# LB_BIT_oX_1IN_1OUT-MEDIUM-v03_1_1x.net
KiCad netlist of a schematic drawn in EAGLE
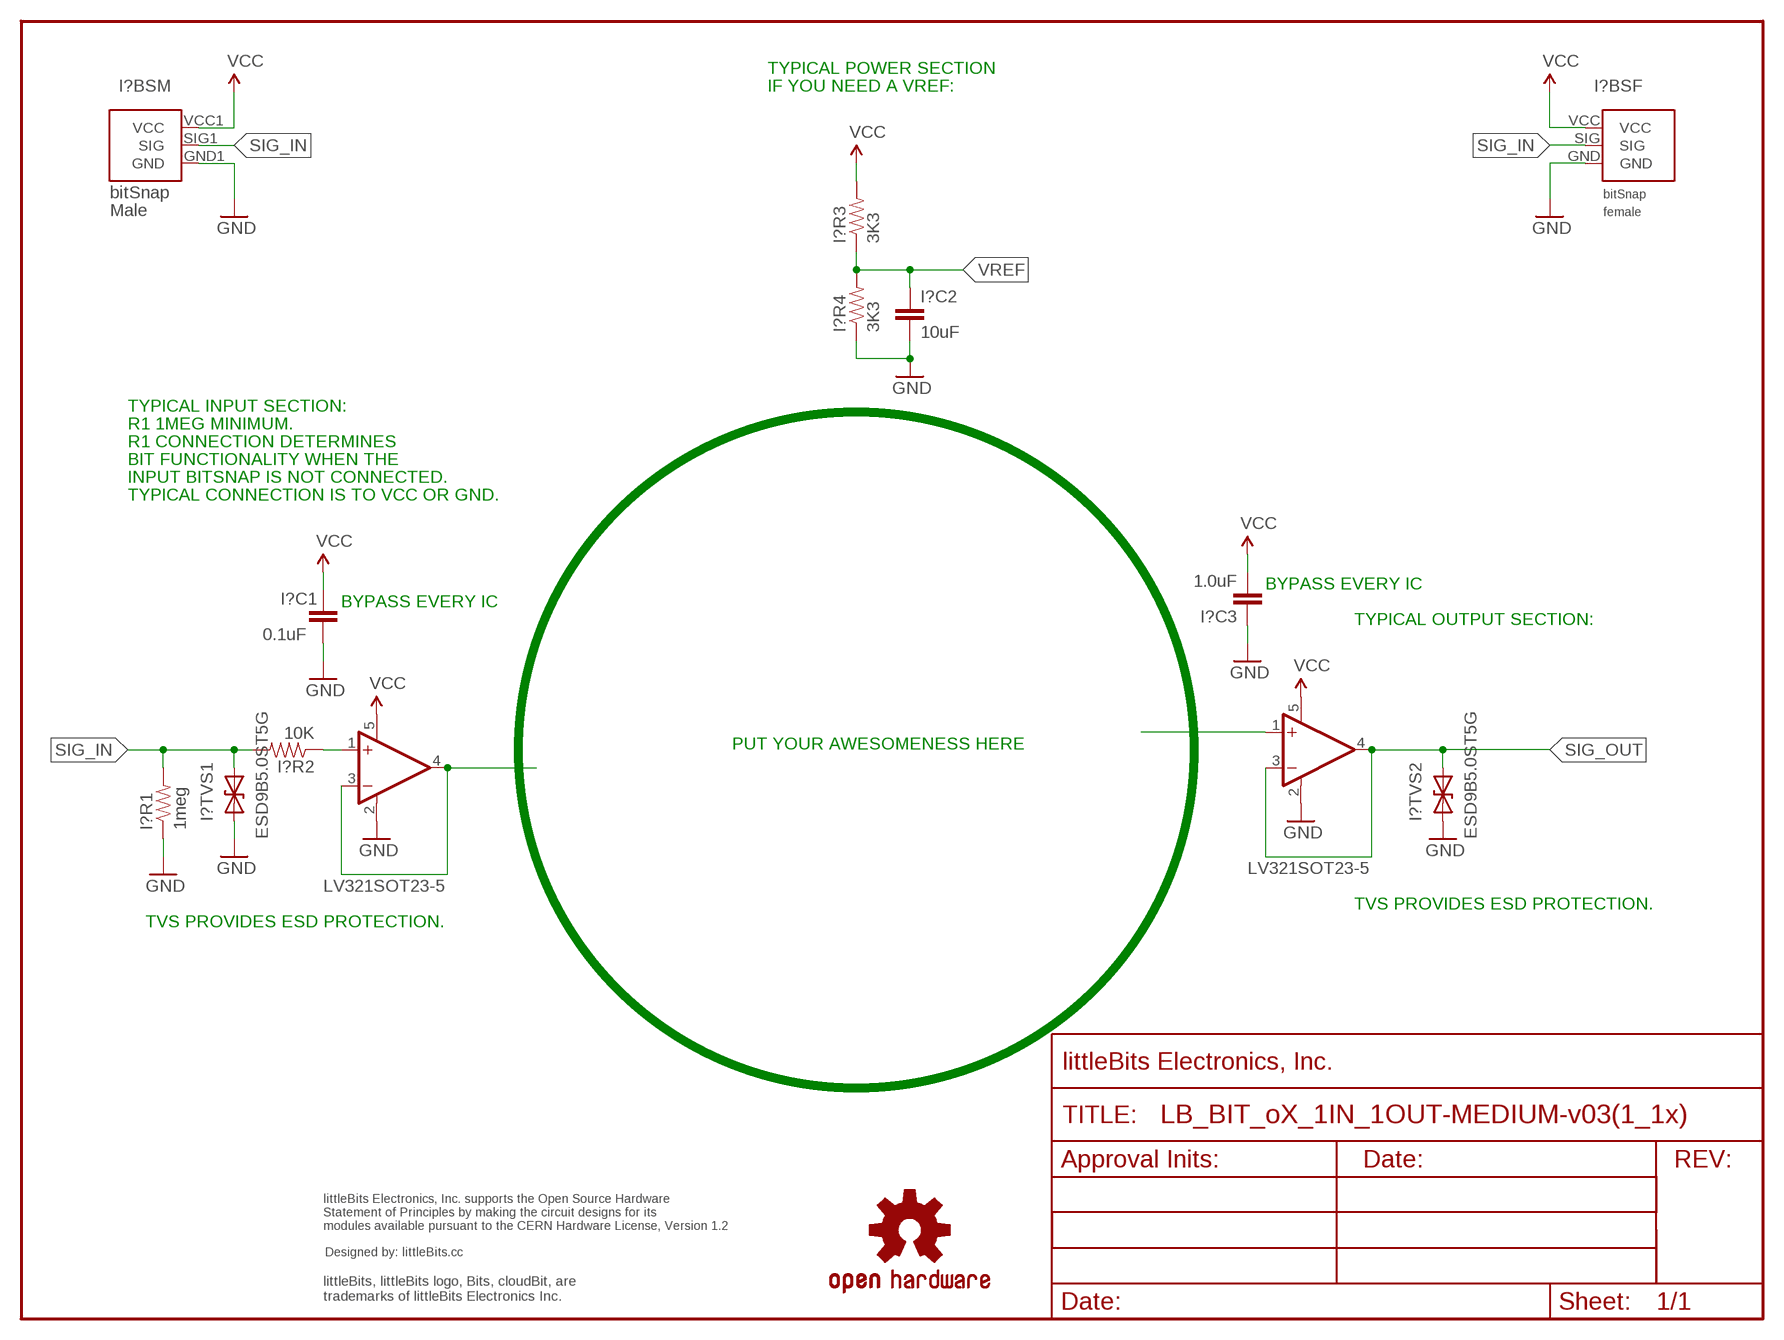
[diagram p0: schematic, sheet 1]

(export (version "E")
  (design (tool "Eeschema 10.0.6"))
  (components
    (comp (ref "I?BSF")
      (value "BITSNAP_V03_FEMALE")
      (footprint "eagle-import:BITSNAP_V03_FEMALE")
      (libsource (lib "eagle-import") (part "BITSNAP_V03_FEMALE"))
    )
    (comp (ref "I?BSM")
      (value "BITSNAP_V03_MALE")
      (footprint "eagle-import:BITSNAP_V03_MALE")
      (libsource (lib "eagle-import") (part "BITSNAP_V03_MALE"))
    )
    (comp (ref "I?C1")
      (value "0.1uF")
      (footprint "eagle-import:CAP-0603")
      (libsource (lib "eagle-import") (part "CAPCAP-0603"))
    )
    (comp (ref "I?C2")
      (value "10uF")
      (footprint "eagle-import:CAP-0603")
      (libsource (lib "eagle-import") (part "CAPCAP-0603"))
    )
    (comp (ref "I?C3")
      (value "1.0uF")
      (footprint "eagle-import:CAP-0603")
      (libsource (lib "eagle-import") (part "CAPCAP-0603"))
    )
    (comp (ref "I?R1")
      (value "1meg")
      (footprint "eagle-import:RES-0603")
      (libsource (lib "eagle-import") (part "RESISTOR0603"))
    )
    (comp (ref "I?R2")
      (value "10K")
      (footprint "eagle-import:RES-0603")
      (libsource (lib "eagle-import") (part "RESISTOR0603"))
    )
    (comp (ref "I?R3")
      (value "3K3")
      (footprint "eagle-import:RES-0603")
      (libsource (lib "eagle-import") (part "RESISTOR0603"))
    )
    (comp (ref "I?R4")
      (value "3K3")
      (footprint "eagle-import:RES-0603")
      (libsource (lib "eagle-import") (part "RESISTOR0603"))
    )
    (comp (ref "I?TVS1")
      (value "ESD9B5.0ST5G")
      (footprint "eagle-import:SOD-923")
      (libsource (lib "eagle-import") (part "DIODE-TVSSOD-923"))
    )
    (comp (ref "I?TVS2")
      (value "ESD9B5.0ST5G")
      (footprint "eagle-import:SOD-923")
      (libsource (lib "eagle-import") (part "DIODE-TVSSOD-923"))
    )
    (comp (ref "U$1")
      (value "FRAME-LETTER")
      (footprint "eagle-import:FABDWG01-OHW")
      (libsource (lib "eagle-import") (part "FRAME-LETTER"))
    )
    (comp (ref "U$2")
      (value "OSHWCREDIT")
      (footprint "eagle-import:OSHWCREDIT")
      (libsource (lib "eagle-import") (part "OSHWCREDIT"))
    )
    (comp (ref "U$3")
      (value "OSHW-LOGOL")
      (footprint "eagle-import:OSHW-LOGO-L")
      (libsource (lib "eagle-import") (part "OSHW-LOGOL"))
    )
    (comp (ref "U1")
      (value "LV321SOT23-5")
      (footprint "eagle-import:SOT23-5")
      (libsource (lib "eagle-import") (part "LV321SOT23-5"))
    )
    (comp (ref "U2")
      (value "LV321SOT23-5")
      (footprint "eagle-import:SOT23-5")
      (libsource (lib "eagle-import") (part "LV321SOT23-5"))
    )
  )
  (nets
    (net (code "1") (name "GND") (class "Default")
      (node (ref "I?BSF") (pin "GND") (pinfunction "GND_GND") (pintype "bidirectional"))
      (node (ref "I?BSM") (pin "GND1") (pinfunction "GND_GND1") (pintype "bidirectional"))
      (node (ref "I?C1") (pin "2") (pinfunction "2_2") (pintype "passive"))
      (node (ref "I?C2") (pin "2") (pinfunction "2_2") (pintype "passive"))
      (node (ref "I?C3") (pin "1") (pinfunction "1_1") (pintype "passive"))
      (node (ref "I?R1") (pin "1") (pinfunction "1_1") (pintype "passive"))
      (node (ref "I?R4") (pin "1") (pinfunction "1_1") (pintype "passive"))
      (node (ref "I?TVS1") (pin "1") (pinfunction "A_1") (pintype "passive"))
      (node (ref "I?TVS2") (pin "1") (pinfunction "A_1") (pintype "passive"))
      (node (ref "U1") (pin "2") (pinfunction "V-_2") (pintype "power_in"))
      (node (ref "U2") (pin "2") (pinfunction "V-_2") (pintype "power_in"))
    )
    (net (code "2") (name "Net-(U1-+IN)") (class "Default")
      (node (ref "I?R2") (pin "1") (pinfunction "1_1") (pintype "passive"))
      (node (ref "U1") (pin "1") (pinfunction "+IN_1") (pintype "input"))
    )
    (net (code "3") (name "Net-(U1--IN)") (class "Default")
      (node (ref "U1") (pin "3") (pinfunction "-IN_3") (pintype "input"))
      (node (ref "U1") (pin "4") (pinfunction "OUT_4") (pintype "output"))
    )
    (net (code "4") (name "SIG_IN") (class "Default")
      (node (ref "I?BSF") (pin "SIG") (pinfunction "SIG_SIG") (pintype "bidirectional"))
      (node (ref "I?BSM") (pin "SIG1") (pinfunction "SIG_SIG1") (pintype "bidirectional"))
      (node (ref "I?R1") (pin "2") (pinfunction "2_2") (pintype "passive"))
      (node (ref "I?R2") (pin "2") (pinfunction "2_2") (pintype "passive"))
      (node (ref "I?TVS1") (pin "2") (pinfunction "C_2") (pintype "passive"))
    )
    (net (code "5") (name "SIG_OUT") (class "Default")
      (node (ref "I?TVS2") (pin "2") (pinfunction "C_2") (pintype "passive"))
      (node (ref "U2") (pin "3") (pinfunction "-IN_3") (pintype "input"))
      (node (ref "U2") (pin "4") (pinfunction "OUT_4") (pintype "output"))
    )
    (net (code "6") (name "VCC") (class "Default")
      (node (ref "I?BSF") (pin "VCC") (pinfunction "VCC_VCC") (pintype "bidirectional"))
      (node (ref "I?BSM") (pin "VCC1") (pinfunction "VCC_VCC1") (pintype "bidirectional"))
      (node (ref "I?C1") (pin "1") (pinfunction "1_1") (pintype "passive"))
      (node (ref "I?C3") (pin "2") (pinfunction "2_2") (pintype "passive"))
      (node (ref "I?R3") (pin "2") (pinfunction "2_2") (pintype "passive"))
      (node (ref "U1") (pin "5") (pinfunction "V+_5") (pintype "power_in"))
      (node (ref "U2") (pin "5") (pinfunction "V+_5") (pintype "power_in"))
    )
    (net (code "7") (name "VREF") (class "Default")
      (node (ref "I?C2") (pin "1") (pinfunction "1_1") (pintype "passive"))
      (node (ref "I?R3") (pin "1") (pinfunction "1_1") (pintype "passive"))
      (node (ref "I?R4") (pin "2") (pinfunction "2_2") (pintype "passive"))
    )
    (net (code "8") (name "unconnected-(U2-+IN-Pad1)") (class "Default")
      (node (ref "U2") (pin "1") (pinfunction "+IN_1") (pintype "input"))
    )
  )
)
